# o_clone_rev_e.net
KiCad netlist of a schematic drawn in EAGLE
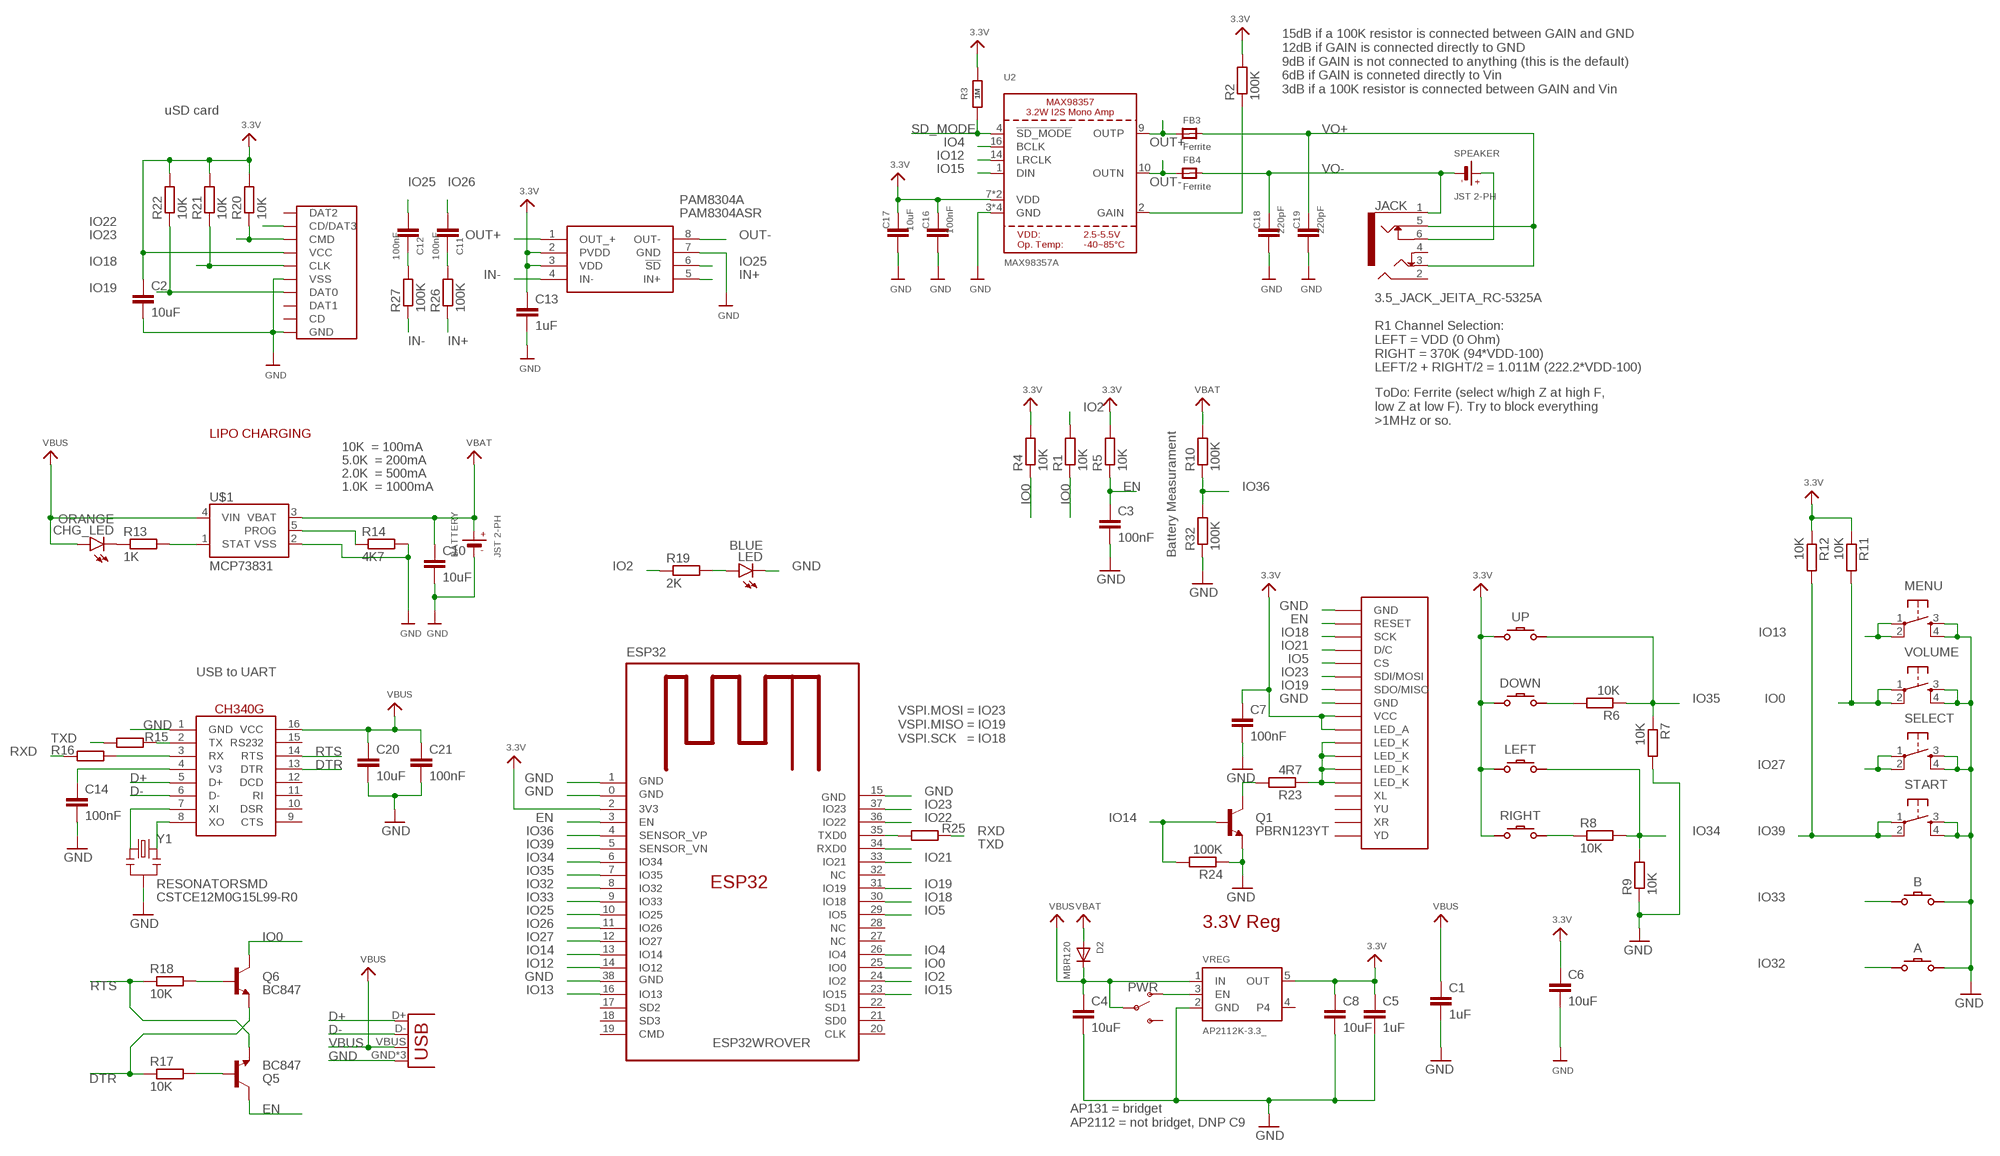
[diagram p0: schematic, sheet 1]

(export (version "E")
  (design (tool "Eeschema 10.0.6"))
  (components
    (comp (ref "A")
      (value "CONDUCTIVE_BUTTON")
      (footprint "eagle-import:CONDUCTIVE_BUTTON")
      (libsource (lib "eagle-import") (part "CONDUCTIVE_BUTTON"))
    )
    (comp (ref "B")
      (value "CONDUCTIVE_BUTTON")
      (footprint "eagle-import:CONDUCTIVE_BUTTON")
      (libsource (lib "eagle-import") (part "CONDUCTIVE_BUTTON"))
    )
    (comp (ref "BATTERY")
      (value "JST 2-PH")
      (footprint "eagle-import:JSTPH2")
      (libsource (lib "eagle-import") (part "JST_CONNECTOR"))
    )
    (comp (ref "C1")
      (value "1uF")
      (footprint "eagle-import:C0805K")
      (libsource (lib "eagle-import") (part "C-EUC0805K"))
    )
    (comp (ref "C2")
      (value "10uF")
      (footprint "eagle-import:C0805K")
      (libsource (lib "eagle-import") (part "C-EUC0805K"))
    )
    (comp (ref "C3")
      (value "100nF")
      (footprint "eagle-import:C0805K")
      (libsource (lib "eagle-import") (part "C-EUC0805K"))
    )
    (comp (ref "C4")
      (value "10uF")
      (footprint "eagle-import:C0805K")
      (libsource (lib "eagle-import") (part "C-EUC0805K"))
    )
    (comp (ref "C5")
      (value "1uF")
      (footprint "eagle-import:C0805K")
      (libsource (lib "eagle-import") (part "C-EUC0805K"))
    )
    (comp (ref "C6")
      (value "10uF")
      (footprint "eagle-import:C0805K")
      (libsource (lib "eagle-import") (part "C-EUC0805K"))
    )
    (comp (ref "C7")
      (value "100nF")
      (footprint "eagle-import:C0805")
      (libsource (lib "eagle-import") (part "C-EUC0805"))
    )
    (comp (ref "C8")
      (value "10uF")
      (footprint "eagle-import:C0805K")
      (libsource (lib "eagle-import") (part "C-EUC0805K"))
    )
    (comp (ref "C10")
      (value "10uF")
      (footprint "eagle-import:C0805K")
      (libsource (lib "eagle-import") (part "C-EUC0805K"))
    )
    (comp (ref "C11")
      (value "100nF")
      (footprint "eagle-import:C0805K")
      (libsource (lib "eagle-import") (part "C-EUC0805K"))
    )
    (comp (ref "C12")
      (value "100nF")
      (footprint "eagle-import:C0805K")
      (libsource (lib "eagle-import") (part "C-EUC0805K"))
    )
    (comp (ref "C13")
      (value "1uF")
      (footprint "eagle-import:C0805K")
      (libsource (lib "eagle-import") (part "C-EUC0805K"))
    )
    (comp (ref "C14")
      (value "100nF")
      (footprint "eagle-import:C0805K")
      (libsource (lib "eagle-import") (part "C-EUC0805K"))
    )
    (comp (ref "C16")
      (value "100nF")
      (footprint "eagle-import:C0805K")
      (libsource (lib "eagle-import") (part "C-EUC0805K"))
    )
    (comp (ref "C17")
      (value "10uF")
      (footprint "eagle-import:C0805K")
      (libsource (lib "eagle-import") (part "C-EUC0805K"))
    )
    (comp (ref "C18")
      (value "220pF")
      (footprint "eagle-import:C0805K")
      (libsource (lib "eagle-import") (part "C-EUC0805K"))
    )
    (comp (ref "C19")
      (value "220pF")
      (footprint "eagle-import:C0805K")
      (libsource (lib "eagle-import") (part "C-EUC0805K"))
    )
    (comp (ref "C20")
      (value "10uF")
      (footprint "eagle-import:C0805K")
      (libsource (lib "eagle-import") (part "C-EUC0805K"))
    )
    (comp (ref "C21")
      (value "100nF")
      (footprint "eagle-import:C0805K")
      (libsource (lib "eagle-import") (part "C-EUC0805K"))
    )
    (comp (ref "CHG_LED")
      (value "ORANGE")
      (footprint "eagle-import:CHIPLED_0805")
      (libsource (lib "eagle-import") (part "LEDCHIPLED_0805"))
    )
    (comp (ref "D2")
      (value "MBR120")
      (footprint "eagle-import:SOD-123")
      (libsource (lib "eagle-import") (part "DIODESOD-123"))
    )
    (comp (ref "DOWN")
      (value "CONDUCTIVE_BUTTON")
      (footprint "eagle-import:CONDUCTIVE_BUTTON")
      (libsource (lib "eagle-import") (part "CONDUCTIVE_BUTTON"))
    )
    (comp (ref "ESP32")
      (value "ESP32WROVER")
      (footprint "eagle-import:ESP32WROVER")
      (libsource (lib "eagle-import") (part "ESP32WROVER"))
    )
    (comp (ref "FB3")
      (value "Ferrite")
      (footprint "eagle-import:0805")
      (libsource (lib "eagle-import") (part "FERRITE0805"))
    )
    (comp (ref "FB4")
      (value "Ferrite")
      (footprint "eagle-import:0805")
      (libsource (lib "eagle-import") (part "FERRITE0805"))
    )
    (comp (ref "JACK")
      (value "3.5_JACK_JEITA_RC-5325A")
      (footprint "eagle-import:3.5_JACK_JEITA_RC-5325A")
      (libsource (lib "eagle-import") (part "3.5_JACK_JEITA_RC-5325A"))
    )
    (comp (ref "LCD")
      (value "ILI9341_3.2LCD_")
      (footprint "eagle-import:LI9341_3.2LCD")
      (libsource (lib "eagle-import") (part "ILI9341_3.2LCD_"))
    )
    (comp (ref "LED")
      (value "BLUE")
      (footprint "eagle-import:CHIPLED_0805")
      (libsource (lib "eagle-import") (part "LEDCHIPLED_0805"))
    )
    (comp (ref "LEFT")
      (value "CONDUCTIVE_BUTTON")
      (footprint "eagle-import:CONDUCTIVE_BUTTON")
      (libsource (lib "eagle-import") (part "CONDUCTIVE_BUTTON"))
    )
    (comp (ref "MENU")
      (value "TACTILE_SWITCHE_5X5_MICRO\"")
      (footprint "eagle-import:TACTILE_SWITCH_5X5_MICRO")
      (libsource (lib "eagle-import") (part "TACTILE_SWITCHE_5X5_MICRO{dblquote}"))
    )
    (comp (ref "PAM8304A")
      (value "PAM8304ASR")
      (footprint "eagle-import:SOP65P490X110-8N")
      (fields (field (name "MOUSER_PART_NUMBER") "621-PAM8304ASR"))
      (libsource (lib "eagle-import") (part "PAM8304ASR"))
    )
    (comp (ref "PWR")
      (value "SWITCH-SPDT-SMD-RIGHT-ANGLE")
      (footprint "eagle-import:SWITCH_SPST_SMD_A")
      (libsource (lib "eagle-import") (part "SWITCH-SPDT-SMD-RIGHT-ANGLE"))
    )
    (comp (ref "Q1")
      (value "PBRN123YT")
      (footprint "eagle-import:SOT23-3")
      (libsource (lib "eagle-import") (part "TRANSISTOR_NPNSOT23-3"))
    )
    (comp (ref "Q5")
      (value "BC847")
      (footprint "eagle-import:SOT23-3")
      (libsource (lib "eagle-import") (part "TRANSISTOR_NPNSOT23-3"))
    )
    (comp (ref "Q6")
      (value "BC847")
      (footprint "eagle-import:SOT23-3")
      (libsource (lib "eagle-import") (part "TRANSISTOR_NPNSOT23-3"))
    )
    (comp (ref "R1")
      (value "10K")
      (footprint "eagle-import:R0805")
      (libsource (lib "eagle-import") (part "R-EU_R0805"))
    )
    (comp (ref "R2")
      (value "100K")
      (footprint "eagle-import:R0805")
      (libsource (lib "eagle-import") (part "R-EU_R0805"))
    )
    (comp (ref "R3")
      (value "1M")
      (footprint "eagle-import:R0805")
      (libsource (lib "eagle-import") (part "R-EU_R0805"))
    )
    (comp (ref "R4")
      (value "10K")
      (footprint "eagle-import:R0805")
      (libsource (lib "eagle-import") (part "R-EU_R0805"))
    )
    (comp (ref "R5")
      (value "10K")
      (footprint "eagle-import:R0805")
      (libsource (lib "eagle-import") (part "R-EU_R0805"))
    )
    (comp (ref "R6")
      (value "10K")
      (footprint "eagle-import:R0805")
      (libsource (lib "eagle-import") (part "R-EU_R0805"))
    )
    (comp (ref "R7")
      (value "10K")
      (footprint "eagle-import:R0805")
      (libsource (lib "eagle-import") (part "R-EU_R0805"))
    )
    (comp (ref "R8")
      (value "10K")
      (footprint "eagle-import:R0805")
      (libsource (lib "eagle-import") (part "R-EU_R0805"))
    )
    (comp (ref "R9")
      (value "10K")
      (footprint "eagle-import:R0805")
      (libsource (lib "eagle-import") (part "R-EU_R0805"))
    )
    (comp (ref "R10")
      (value "100K")
      (footprint "eagle-import:R0805")
      (libsource (lib "eagle-import") (part "R-EU_R0805"))
    )
    (comp (ref "R11")
      (value "10K")
      (footprint "eagle-import:R0805")
      (libsource (lib "eagle-import") (part "R-EU_R0805"))
    )
    (comp (ref "R12")
      (value "10K")
      (footprint "eagle-import:R0805")
      (libsource (lib "eagle-import") (part "R-EU_R0805"))
    )
    (comp (ref "R13")
      (value "1K")
      (footprint "eagle-import:R0805")
      (libsource (lib "eagle-import") (part "R-EU_R0805"))
    )
    (comp (ref "R14")
      (value "4K7")
      (footprint "eagle-import:R0805")
      (libsource (lib "eagle-import") (part "R-EU_R0805"))
    )
    (comp (ref "R15")
      (value "470R")
      (footprint "eagle-import:R0805")
      (libsource (lib "eagle-import") (part "R-EU_R0805"))
    )
    (comp (ref "R16")
      (value "470R")
      (footprint "eagle-import:R0805")
      (libsource (lib "eagle-import") (part "R-EU_R0805"))
    )
    (comp (ref "R17")
      (value "10K")
      (footprint "eagle-import:R0805")
      (libsource (lib "eagle-import") (part "R-EU_R0805"))
    )
    (comp (ref "R18")
      (value "10K")
      (footprint "eagle-import:R0805")
      (libsource (lib "eagle-import") (part "R-EU_R0805"))
    )
    (comp (ref "R19")
      (value "2K")
      (footprint "eagle-import:R0805")
      (libsource (lib "eagle-import") (part "R-EU_R0805"))
    )
    (comp (ref "R20")
      (value "10K")
      (footprint "eagle-import:R0805")
      (libsource (lib "eagle-import") (part "R-EU_R0805"))
    )
    (comp (ref "R21")
      (value "10K")
      (footprint "eagle-import:R0805")
      (libsource (lib "eagle-import") (part "R-EU_R0805"))
    )
    (comp (ref "R22")
      (value "10K")
      (footprint "eagle-import:R0805")
      (libsource (lib "eagle-import") (part "R-EU_R0805"))
    )
    (comp (ref "R23")
      (value "4R7")
      (footprint "eagle-import:R0805")
      (libsource (lib "eagle-import") (part "R-EU_R0805"))
    )
    (comp (ref "R24")
      (value "100K")
      (footprint "eagle-import:R0805")
      (libsource (lib "eagle-import") (part "R-EU_R0805"))
    )
    (comp (ref "R25")
      (value "470R")
      (footprint "eagle-import:R0805")
      (libsource (lib "eagle-import") (part "R-EU_R0805"))
    )
    (comp (ref "R26")
      (value "100K")
      (footprint "eagle-import:R0805")
      (libsource (lib "eagle-import") (part "R-EU_R0805"))
    )
    (comp (ref "R27")
      (value "100K")
      (footprint "eagle-import:R0805")
      (libsource (lib "eagle-import") (part "R-EU_R0805"))
    )
    (comp (ref "R32")
      (value "100K")
      (footprint "eagle-import:R0805")
      (libsource (lib "eagle-import") (part "R-EU_R0805"))
    )
    (comp (ref "RIGHT")
      (value "CONDUCTIVE_BUTTON")
      (footprint "eagle-import:CONDUCTIVE_BUTTON")
      (libsource (lib "eagle-import") (part "CONDUCTIVE_BUTTON"))
    )
    (comp (ref "SD_CARD")
      (value "MICRO_SD_CARD\"")
      (footprint "eagle-import:TFP09-2--12B")
      (libsource (lib "eagle-import") (part "MICRO_SD_CARD{dblquote}"))
    )
    (comp (ref "SELECT")
      (value "TACTILE_SWITCHE_5X5_MICRO\"")
      (footprint "eagle-import:TACTILE_SWITCH_5X5_MICRO")
      (libsource (lib "eagle-import") (part "TACTILE_SWITCHE_5X5_MICRO{dblquote}"))
    )
    (comp (ref "SPEAKER")
      (value "JST 2-PH")
      (footprint "eagle-import:JSTPH2")
      (libsource (lib "eagle-import") (part "JST_CONNECTOR"))
    )
    (comp (ref "START")
      (value "TACTILE_SWITCHE_5X5_MICRO\"")
      (footprint "eagle-import:TACTILE_SWITCH_5X5_MICRO")
      (libsource (lib "eagle-import") (part "TACTILE_SWITCHE_5X5_MICRO{dblquote}"))
    )
    (comp (ref "U$1")
      (value "MCP73831")
      (footprint "eagle-import:SOT95P290X120-5")
      (libsource (lib "eagle-import") (part "MCP73831"))
    )
    (comp (ref "U$23")
      (value "CH340G")
      (footprint "eagle-import:SO16")
      (libsource (lib "eagle-import") (part "CH340G"))
    )
    (comp (ref "U2")
      (value "MAX98357A")
      (footprint "eagle-import:QFN16_3MM")
      (libsource (lib "eagle-import") (part "AUDIOAMP_MAX98357"))
    )
    (comp (ref "UP")
      (value "CONDUCTIVE_BUTTON")
      (footprint "eagle-import:CONDUCTIVE_BUTTON")
      (libsource (lib "eagle-import") (part "CONDUCTIVE_BUTTON"))
    )
    (comp (ref "USB")
      (value "USB_MICRO_ATTEND_")
      (footprint "eagle-import:USB_MICRO")
      (libsource (lib "eagle-import") (part "USB_MICRO_ATTEND_"))
    )
    (comp (ref "VOLUME")
      (value "TACTILE_SWITCHE_5X5_MICRO\"")
      (footprint "eagle-import:TACTILE_SWITCH_5X5_MICRO")
      (libsource (lib "eagle-import") (part "TACTILE_SWITCHE_5X5_MICRO{dblquote}"))
    )
    (comp (ref "VREG")
      (value "AP2112K-3.3_")
      (footprint "eagle-import:SOT95P290X120-5")
      (libsource (lib "eagle-import") (part "AP2112K-3.3_"))
    )
    (comp (ref "Y1")
      (value "RESONATORSMD")
      (footprint "eagle-import:RESONATOR-SMD")
      (libsource (lib "eagle-import") (part "RESONATORSMD"))
    )
  )
  (nets
    (net (code "1") (name "/D+") (class "Default")
      (node (ref "U$23") (pin "5") (pinfunction "D+_5") (pintype "bidirectional"))
      (node (ref "USB") (pin "D+") (pinfunction "D+_D+") (pintype "bidirectional"))
    )
    (net (code "2") (name "/D-") (class "Default")
      (node (ref "U$23") (pin "6") (pinfunction "D-_6") (pintype "bidirectional"))
      (node (ref "USB") (pin "D-") (pinfunction "D-_D-") (pintype "bidirectional"))
    )
    (net (code "3") (name "/DTR") (class "Default")
      (node (ref "Q6") (pin "2") (pinfunction "E_2") (pintype "passive"))
      (node (ref "R17") (pin "1") (pinfunction "1_1") (pintype "passive"))
      (node (ref "U$23") (pin "13") (pinfunction "DTR_13") (pintype "bidirectional"))
    )
    (net (code "4") (name "/EN") (class "Default")
      (node (ref "C3") (pin "1") (pinfunction "1_1") (pintype "passive"))
      (node (ref "ESP32") (pin "3") (pinfunction "EN_3") (pintype "bidirectional"))
      (node (ref "LCD") (pin "P$2") (pinfunction "RESET_P$2") (pintype "bidirectional"))
      (node (ref "Q5") (pin "3") (pinfunction "C_3") (pintype "passive"))
      (node (ref "R5") (pin "1") (pinfunction "1_1") (pintype "passive"))
    )
    (net (code "5") (name "/IN+") (class "Default")
      (node (ref "PAM8304A") (pin "5") (pinfunction "IN+_5") (pintype "bidirectional"))
      (node (ref "R26") (pin "1") (pinfunction "1_1") (pintype "passive"))
    )
    (net (code "6") (name "/IN-") (class "Default")
      (node (ref "PAM8304A") (pin "4") (pinfunction "IN-_4") (pintype "bidirectional"))
      (node (ref "R27") (pin "1") (pinfunction "1_1") (pintype "passive"))
    )
    (net (code "7") (name "/IO0") (class "Default")
      (node (ref "ESP32") (pin "25") (pinfunction "IO0_25") (pintype "bidirectional"))
      (node (ref "Q6") (pin "3") (pinfunction "C_3") (pintype "passive"))
      (node (ref "R1") (pin "1") (pinfunction "1_1") (pintype "passive"))
      (node (ref "R11") (pin "2") (pinfunction "2_2") (pintype "passive"))
      (node (ref "R4") (pin "1") (pinfunction "1_1") (pintype "passive"))
      (node (ref "VOLUME") (pin "1") (pinfunction "1_1") (pintype "passive"))
      (node (ref "VOLUME") (pin "2") (pinfunction "2_2") (pintype "passive"))
    )
    (net (code "8") (name "/IO2") (class "Default")
      (node (ref "ESP32") (pin "24") (pinfunction "IO2_24") (pintype "bidirectional"))
      (node (ref "R1") (pin "2") (pinfunction "2_2") (pintype "passive"))
      (node (ref "R19") (pin "1") (pinfunction "1_1") (pintype "passive"))
    )
    (net (code "9") (name "/IO4") (class "Default")
      (node (ref "ESP32") (pin "26") (pinfunction "IO4_26") (pintype "bidirectional"))
      (node (ref "U2") (pin "16") (pinfunction "BCLK_16") (pintype "bidirectional"))
    )
    (net (code "10") (name "/IO5") (class "Default")
      (node (ref "ESP32") (pin "29") (pinfunction "IO5_29") (pintype "bidirectional"))
      (node (ref "LCD") (pin "P$5") (pinfunction "CS_P$5") (pintype "bidirectional"))
    )
    (net (code "11") (name "/IO12") (class "Default")
      (node (ref "ESP32") (pin "14") (pinfunction "IO12_14") (pintype "bidirectional"))
      (node (ref "U2") (pin "14") (pinfunction "LRCLK_14") (pintype "bidirectional"))
    )
    (net (code "12") (name "/IO13") (class "Default")
      (node (ref "ESP32") (pin "16") (pinfunction "IO13_16") (pintype "bidirectional"))
      (node (ref "MENU") (pin "1") (pinfunction "1_1") (pintype "passive"))
      (node (ref "MENU") (pin "2") (pinfunction "2_2") (pintype "passive"))
    )
    (net (code "13") (name "/IO14") (class "Default")
      (node (ref "ESP32") (pin "13") (pinfunction "IO14_13") (pintype "bidirectional"))
      (node (ref "Q1") (pin "1") (pinfunction "B_1") (pintype "passive"))
      (node (ref "R24") (pin "2") (pinfunction "2_2") (pintype "passive"))
    )
    (net (code "14") (name "/IO15") (class "Default")
      (node (ref "ESP32") (pin "23") (pinfunction "IO15_23") (pintype "bidirectional"))
      (node (ref "U2") (pin "1") (pinfunction "DIN_1") (pintype "bidirectional"))
    )
    (net (code "15") (name "/IO18") (class "Default")
      (node (ref "ESP32") (pin "30") (pinfunction "IO18_30") (pintype "bidirectional"))
      (node (ref "LCD") (pin "P$3") (pinfunction "SCK_P$3") (pintype "bidirectional"))
      (node (ref "R21") (pin "1") (pinfunction "1_1") (pintype "passive"))
      (node (ref "SD_CARD") (pin "CLK") (pinfunction "CLK_CLK") (pintype "bidirectional"))
    )
    (net (code "16") (name "/IO19") (class "Default")
      (node (ref "ESP32") (pin "31") (pinfunction "IO19_31") (pintype "bidirectional"))
      (node (ref "LCD") (pin "P$7") (pinfunction "SDO/MISO_P$7") (pintype "bidirectional"))
      (node (ref "R22") (pin "1") (pinfunction "1_1") (pintype "passive"))
      (node (ref "SD_CARD") (pin "DAT0") (pinfunction "DAT0_DAT0") (pintype "bidirectional"))
    )
    (net (code "17") (name "/IO21") (class "Default")
      (node (ref "ESP32") (pin "33") (pinfunction "IO21_33") (pintype "bidirectional"))
      (node (ref "LCD") (pin "P$4") (pinfunction "D/C_P$4") (pintype "bidirectional"))
    )
    (net (code "18") (name "/IO22") (class "Default")
      (node (ref "ESP32") (pin "36") (pinfunction "IO22_36") (pintype "bidirectional"))
      (node (ref "SD_CARD") (pin "CD/DAT3") (pinfunction "CD/DAT3_CD/DAT3") (pintype "bidirectional"))
    )
    (net (code "19") (name "/IO23") (class "Default")
      (node (ref "ESP32") (pin "37") (pinfunction "IO23_37") (pintype "bidirectional"))
      (node (ref "LCD") (pin "P$6") (pinfunction "SDI/MOSI_P$6") (pintype "bidirectional"))
      (node (ref "R20") (pin "1") (pinfunction "1_1") (pintype "passive"))
      (node (ref "SD_CARD") (pin "CMD") (pinfunction "CMD_CMD") (pintype "bidirectional"))
    )
    (net (code "20") (name "/IO25") (class "Default")
      (node (ref "C12") (pin "2") (pinfunction "2_2") (pintype "passive"))
      (node (ref "ESP32") (pin "10") (pinfunction "IO25_10") (pintype "bidirectional"))
      (node (ref "PAM8304A") (pin "6") (pinfunction "~{SD}_6") (pintype "bidirectional"))
    )
    (net (code "21") (name "/IO26") (class "Default")
      (node (ref "C11") (pin "2") (pinfunction "2_2") (pintype "passive"))
      (node (ref "ESP32") (pin "11") (pinfunction "IO26_11") (pintype "bidirectional"))
    )
    (net (code "22") (name "/IO27") (class "Default")
      (node (ref "ESP32") (pin "12") (pinfunction "IO27_12") (pintype "bidirectional"))
      (node (ref "SELECT") (pin "1") (pinfunction "1_1") (pintype "passive"))
      (node (ref "SELECT") (pin "2") (pinfunction "2_2") (pintype "passive"))
    )
    (net (code "23") (name "/IO32") (class "Default")
      (node (ref "A") (pin "P$1") (pinfunction "P$1_P$1") (pintype "bidirectional"))
      (node (ref "ESP32") (pin "8") (pinfunction "IO32_8") (pintype "bidirectional"))
    )
    (net (code "24") (name "/IO33") (class "Default")
      (node (ref "B") (pin "P$1") (pinfunction "P$1_P$1") (pintype "bidirectional"))
      (node (ref "ESP32") (pin "9") (pinfunction "IO33_9") (pintype "bidirectional"))
    )
    (net (code "25") (name "/IO34") (class "Default")
      (node (ref "ESP32") (pin "6") (pinfunction "IO34_6") (pintype "bidirectional"))
      (node (ref "LEFT") (pin "P$2") (pinfunction "P$2_P$2") (pintype "bidirectional"))
      (node (ref "R8") (pin "2") (pinfunction "2_2") (pintype "passive"))
      (node (ref "R9") (pin "2") (pinfunction "2_2") (pintype "passive"))
    )
    (net (code "26") (name "/IO35") (class "Default")
      (node (ref "ESP32") (pin "7") (pinfunction "IO35_7") (pintype "bidirectional"))
      (node (ref "R6") (pin "1") (pinfunction "1_1") (pintype "passive"))
      (node (ref "R7") (pin "1") (pinfunction "1_1") (pintype "passive"))
      (node (ref "UP") (pin "P$2") (pinfunction "P$2_P$2") (pintype "bidirectional"))
    )
    (net (code "27") (name "/IO36") (class "Default")
      (node (ref "ESP32") (pin "4") (pinfunction "SENSOR_VP_4") (pintype "bidirectional"))
      (node (ref "R10") (pin "1") (pinfunction "1_1") (pintype "passive"))
      (node (ref "R32") (pin "2") (pinfunction "2_2") (pintype "passive"))
    )
    (net (code "28") (name "/IO39") (class "Default")
      (node (ref "ESP32") (pin "5") (pinfunction "SENSOR_VN_5") (pintype "bidirectional"))
      (node (ref "R12") (pin "2") (pinfunction "2_2") (pintype "passive"))
      (node (ref "START") (pin "1") (pinfunction "1_1") (pintype "passive"))
      (node (ref "START") (pin "2") (pinfunction "2_2") (pintype "passive"))
    )
    (net (code "29") (name "/OUT+") (class "Default")
      (node (ref "FB3") (pin "1") (pinfunction "P$1_1") (pintype "passive"))
      (node (ref "PAM8304A") (pin "1") (pinfunction "OUT_+_1") (pintype "bidirectional"))
      (node (ref "U2") (pin "9") (pinfunction "OUTP_9") (pintype "output"))
    )
    (net (code "30") (name "/OUT-") (class "Default")
      (node (ref "FB4") (pin "1") (pinfunction "P$1_1") (pintype "passive"))
      (node (ref "PAM8304A") (pin "8") (pinfunction "OUT-_8") (pintype "bidirectional"))
      (node (ref "U2") (pin "10") (pinfunction "OUTN_10") (pintype "output"))
    )
    (net (code "31") (name "/RTS") (class "Default")
      (node (ref "Q5") (pin "2") (pinfunction "E_2") (pintype "passive"))
      (node (ref "R18") (pin "1") (pinfunction "1_1") (pintype "passive"))
      (node (ref "U$23") (pin "14") (pinfunction "RTS_14") (pintype "bidirectional"))
    )
    (net (code "32") (name "/RXD") (class "Default")
      (node (ref "R16") (pin "2") (pinfunction "2_2") (pintype "passive"))
      (node (ref "R25") (pin "1") (pinfunction "1_1") (pintype "passive"))
    )
    (net (code "33") (name "/SD_MODE") (class "Default")
      (node (ref "R3") (pin "1") (pinfunction "1_1") (pintype "passive"))
      (node (ref "U2") (pin "4") (pinfunction "~{SD_MODE}_4") (pintype "bidirectional"))
    )
    (net (code "34") (name "/TXD") (class "Default")
      (node (ref "ESP32") (pin "34") (pinfunction "RXD0_34") (pintype "bidirectional"))
      (node (ref "R15") (pin "2") (pinfunction "2_2") (pintype "passive"))
    )
    (net (code "35") (name "/VO+") (class "Default")
      (node (ref "C19") (pin "1") (pinfunction "1_1") (pintype "passive"))
      (node (ref "FB3") (pin "2") (pinfunction "P$2_2") (pintype "passive"))
      (node (ref "JACK") (pin "3") (pinfunction "3_3") (pintype "bidirectional"))
      (node (ref "JACK") (pin "5") (pinfunction "5_5") (pintype "bidirectional"))
    )
    (net (code "36") (name "/VO-") (class "Default")
      (node (ref "C18") (pin "1") (pinfunction "1_1") (pintype "passive"))
      (node (ref "FB4") (pin "2") (pinfunction "P$2_2") (pintype "passive"))
      (node (ref "JACK") (pin "1") (pinfunction "1_1") (pintype "bidirectional"))
      (node (ref "SPEAKER") (pin "1") (pinfunction "-_1") (pintype "passive"))
    )
    (net (code "37") (name "3.3V") (class "Default")
      (node (ref "C13") (pin "1") (pinfunction "1_1") (pintype "passive"))
      (node (ref "C16") (pin "1") (pinfunction "1_1") (pintype "passive"))
      (node (ref "C17") (pin "1") (pinfunction "1_1") (pintype "passive"))
      (node (ref "C2") (pin "1") (pinfunction "1_1") (pintype "passive"))
      (node (ref "C5") (pin "1") (pinfunction "1_1") (pintype "passive"))
      (node (ref "C6") (pin "1") (pinfunction "1_1") (pintype "passive"))
      (node (ref "C7") (pin "1") (pinfunction "1_1") (pintype "passive"))
      (node (ref "C8") (pin "1") (pinfunction "1_1") (pintype "passive"))
      (node (ref "DOWN") (pin "P$1") (pinfunction "P$1_P$1") (pintype "bidirectional"))
      (node (ref "ESP32") (pin "2") (pinfunction "3V3_2") (pintype "power_in"))
      (node (ref "LCD") (pin "P$10") (pinfunction "LED_A_P$10") (pintype "bidirectional"))
      (node (ref "LCD") (pin "P$9") (pinfunction "VCC_P$9") (pintype "bidirectional"))
      (node (ref "LEFT") (pin "P$1") (pinfunction "P$1_P$1") (pintype "bidirectional"))
      (node (ref "PAM8304A") (pin "2") (pinfunction "PVDD_2") (pintype "bidirectional"))
      (node (ref "PAM8304A") (pin "3") (pinfunction "VDD_3") (pintype "bidirectional"))
      (node (ref "R11") (pin "1") (pinfunction "1_1") (pintype "passive"))
      (node (ref "R12") (pin "1") (pinfunction "1_1") (pintype "passive"))
      (node (ref "R2") (pin "2") (pinfunction "2_2") (pintype "passive"))
      (node (ref "R20") (pin "2") (pinfunction "2_2") (pintype "passive"))
      (node (ref "R21") (pin "2") (pinfunction "2_2") (pintype "passive"))
      (node (ref "R22") (pin "2") (pinfunction "2_2") (pintype "passive"))
      (node (ref "R3") (pin "2") (pinfunction "2_2") (pintype "passive"))
      (node (ref "R4") (pin "2") (pinfunction "2_2") (pintype "passive"))
      (node (ref "R5") (pin "2") (pinfunction "2_2") (pintype "passive"))
      (node (ref "RIGHT") (pin "P$1") (pinfunction "P$1_P$1") (pintype "bidirectional"))
      (node (ref "SD_CARD") (pin "VCC") (pinfunction "VCC_VCC") (pintype "bidirectional"))
      (node (ref "U2") (pin "7") (pinfunction "VDD_7") (pintype "power_in"))
      (node (ref "U2") (pin "8") (pinfunction "VDD_8") (pintype "power_in"))
      (node (ref "UP") (pin "P$1") (pinfunction "P$1_P$1") (pintype "bidirectional"))
      (node (ref "VREG") (pin "5") (pinfunction "OUT_5") (pintype "bidirectional"))
    )
    (net (code "38") (name "GND") (class "Default")
      (node (ref "A") (pin "P$2") (pinfunction "P$2_P$2") (pintype "bidirectional"))
      (node (ref "B") (pin "P$2") (pinfunction "P$2_P$2") (pintype "bidirectional"))
      (node (ref "BATTERY") (pin "1") (pinfunction "-_1") (pintype "passive"))
      (node (ref "C1") (pin "2") (pinfunction "2_2") (pintype "passive"))
      (node (ref "C10") (pin "2") (pinfunction "2_2") (pintype "passive"))
      (node (ref "C13") (pin "2") (pinfunction "2_2") (pintype "passive"))
      (node (ref "C14") (pin "2") (pinfunction "2_2") (pintype "passive"))
      (node (ref "C16") (pin "2") (pinfunction "2_2") (pintype "passive"))
      (node (ref "C17") (pin "2") (pinfunction "2_2") (pintype "passive"))
      (node (ref "C18") (pin "2") (pinfunction "2_2") (pintype "passive"))
      (node (ref "C19") (pin "2") (pinfunction "2_2") (pintype "passive"))
      (node (ref "C2") (pin "2") (pinfunction "2_2") (pintype "passive"))
      (node (ref "C20") (pin "2") (pinfunction "2_2") (pintype "passive"))
      (node (ref "C21") (pin "2") (pinfunction "2_2") (pintype "passive"))
      (node (ref "C3") (pin "2") (pinfunction "2_2") (pintype "passive"))
      (node (ref "C4") (pin "2") (pinfunction "2_2") (pintype "passive"))
      (node (ref "C5") (pin "2") (pinfunction "2_2") (pintype "passive"))
      (node (ref "C6") (pin "2") (pinfunction "2_2") (pintype "passive"))
      (node (ref "C7") (pin "2") (pinfunction "2_2") (pintype "passive"))
      (node (ref "C8") (pin "2") (pinfunction "2_2") (pintype "passive"))
      (node (ref "ESP32") (pin "0") (pinfunction "GND_0") (pintype "power_in"))
      (node (ref "ESP32") (pin "1") (pinfunction "GND_1") (pintype "power_in"))
      (node (ref "ESP32") (pin "15") (pinfunction "GND_15") (pintype "power_in"))
      (node (ref "ESP32") (pin "38") (pinfunction "GND_38") (pintype "power_in"))
      (node (ref "LCD") (pin "P$1") (pinfunction "GND_P$1") (pintype "bidirectional"))
      (node (ref "LCD") (pin "P$8") (pinfunction "GND_P$8") (pintype "bidirectional"))
      (node (ref "LED") (pin "C") (pinfunction "C_C") (pintype "passive"))
      (node (ref "MENU") (pin "3") (pinfunction "3_3") (pintype "passive"))
      (node (ref "MENU") (pin "4") (pinfunction "4_4") (pintype "passive"))
      (node (ref "PAM8304A") (pin "7") (pinfunction "GND_7") (pintype "bidirectional"))
      (node (ref "Q1") (pin "2") (pinfunction "E_2") (pintype "passive"))
      (node (ref "R14") (pin "2") (pinfunction "2_2") (pintype "passive"))
      (node (ref "R24") (pin "1") (pinfunction "1_1") (pintype "passive"))
      (node (ref "R32") (pin "1") (pinfunction "1_1") (pintype "passive"))
      (node (ref "R7") (pin "2") (pinfunction "2_2") (pintype "passive"))
      (node (ref "R9") (pin "1") (pinfunction "1_1") (pintype "passive"))
      (node (ref "SD_CARD") (pin "GND") (pinfunction "GND_GND") (pintype "bidirectional"))
      (node (ref "SD_CARD") (pin "GND@1") (pinfunction "GND_GND@1") (pintype "bidirectional"))
      (node (ref "SD_CARD") (pin "GND@2") (pinfunction "GND_GND@2") (pintype "bidirectional"))
      (node (ref "SD_CARD") (pin "GND@3") (pinfunction "VSS_GND@3") (pintype "bidirectional"))
      (node (ref "SD_CARD") (pin "VSS") (pinfunction "GND_VSS") (pintype "bidirectional"))
      (node (ref "SELECT") (pin "3") (pinfunction "3_3") (pintype "passive"))
      (node (ref "SELECT") (pin "4") (pinfunction "4_4") (pintype "passive"))
      (node (ref "START") (pin "3") (pinfunction "3_3") (pintype "passive"))
      (node (ref "START") (pin "4") (pinfunction "4_4") (pintype "passive"))
      (node (ref "U$1") (pin "2") (pinfunction "VSS_2") (pintype "power_in"))
      (node (ref "U$23") (pin "1") (pinfunction "GND_1") (pintype "bidirectional"))
      (node (ref "U2") (pin "11") (pinfunction "GND_11") (pintype "power_in"))
      (node (ref "U2") (pin "15") (pinfunction "GND_15") (pintype "power_in"))
      (node (ref "U2") (pin "3") (pinfunction "GND_3") (pintype "power_in"))
      (node (ref "U2") (pin "THERMAL") (pinfunction "GND_THERMAL") (pintype "power_in"))
      (node (ref "USB") (pin "GND") (pinfunction "GND_GND") (pintype "bidirectional"))
      (node (ref "USB") (pin "GND@2") (pinfunction "GND_GND@2") (pintype "bidirectional"))
      (node (ref "USB") (pin "GND@3") (pinfunction "GND_GND@3") (pintype "bidirectional"))
      (node (ref "VOLUME") (pin "3") (pinfunction "3_3") (pintype "passive"))
      (node (ref "VOLUME") (pin "4") (pinfunction "4_4") (pintype "passive"))
      (node (ref "VREG") (pin "2") (pinfunction "GND_2") (pintype "bidirectional"))
      (node (ref "Y1") (pin "2") (pinfunction "2_2") (pintype "passive"))
    )
    (net (code "39") (name "Net-(C11-Pad1)") (class "Default")
      (node (ref "C11") (pin "1") (pinfunction "1_1") (pintype "passive"))
      (node (ref "R26") (pin "2") (pinfunction "2_2") (pintype "passive"))
    )
    (net (code "40") (name "Net-(C12-Pad1)") (class "Default")
      (node (ref "C12") (pin "1") (pinfunction "1_1") (pintype "passive"))
      (node (ref "R27") (pin "2") (pinfunction "2_2") (pintype "passive"))
    )
    (net (code "41") (name "Net-(CHG_LED-PadC)") (class "Default")
      (node (ref "CHG_LED") (pin "C") (pinfunction "C_C") (pintype "passive"))
      (node (ref "R13") (pin "1") (pinfunction "1_1") (pintype "passive"))
    )
    (net (code "42") (name "Net-(DOWN-PadP$2)") (class "Default")
      (node (ref "DOWN") (pin "P$2") (pinfunction "P$2_P$2") (pintype "bidirectional"))
      (node (ref "R6") (pin "2") (pinfunction "2_2") (pintype "passive"))
    )
    (net (code "43") (name "Net-(ESP32-TXD0)") (class "Default")
      (node (ref "ESP32") (pin "35") (pinfunction "TXD0_35") (pintype "bidirectional"))
      (node (ref "R25") (pin "2") (pinfunction "2_2") (pintype "passive"))
    )
    (net (code "44") (name "Net-(LCD-LED_K-PadP$11)") (class "Default")
      (node (ref "LCD") (pin "P$11") (pinfunction "LED_K_P$11") (pintype "bidirectional"))
      (node (ref "LCD") (pin "P$12") (pinfunction "LED_K_P$12") (pintype "bidirectional"))
      (node (ref "LCD") (pin "P$13") (pinfunction "LED_K_P$13") (pintype "bidirectional"))
      (node (ref "LCD") (pin "P$14") (pinfunction "LED_K_P$14") (pintype "bidirectional"))
      (node (ref "R23") (pin "1") (pinfunction "1_1") (pintype "passive"))
    )
    (net (code "45") (name "Net-(LED-PadA)") (class "Default")
      (node (ref "LED") (pin "A") (pinfunction "A_A") (pintype "passive"))
      (node (ref "R19") (pin "2") (pinfunction "2_2") (pintype "passive"))
    )
    (net (code "46") (name "Net-(PWR-O)") (class "Default")
      (node (ref "PWR") (pin "1") (pinfunction "O_1") (pintype "passive"))
      (node (ref "VREG") (pin "3") (pinfunction "EN_3") (pintype "bidirectional"))
    )
    (net (code "47") (name "Net-(Q1-C)") (class "Default")
      (node (ref "Q1") (pin "3") (pinfunction "C_3") (pintype "passive"))
      (node (ref "R23") (pin "2") (pinfunction "2_2") (pintype "passive"))
    )
    (net (code "48") (name "Net-(Q5-B)") (class "Default")
      (node (ref "Q5") (pin "1") (pinfunction "B_1") (pintype "passive"))
      (node (ref "R17") (pin "2") (pinfunction "2_2") (pintype "passive"))
    )
    (net (code "49") (name "Net-(Q6-B)") (class "Default")
      (node (ref "Q6") (pin "1") (pinfunction "B_1") (pintype "passive"))
      (node (ref "R18") (pin "2") (pinfunction "2_2") (pintype "passive"))
    )
    (net (code "50") (name "Net-(R8-Pad1)") (class "Default")
      (node (ref "R8") (pin "1") (pinfunction "1_1") (pintype "passive"))
      (node (ref "RIGHT") (pin "P$2") (pinfunction "P$2_P$2") (pintype "bidirectional"))
    )
    (net (code "51") (name "Net-(SPEAKER-+)") (class "Default")
      (node (ref "JACK") (pin "6") (pinfunction "6_6") (pintype "bidirectional"))
      (node (ref "SPEAKER") (pin "2") (pinfunction "+_2") (pintype "passive"))
    )
    (net (code "52") (name "Net-(U$1-PROG)") (class "Default")
      (node (ref "R14") (pin "1") (pinfunction "1_1") (pintype "passive"))
      (node (ref "U$1") (pin "5") (pinfunction "PROG_5") (pintype "input"))
    )
    (net (code "53") (name "Net-(U$1-STAT)") (class "Default")
      (node (ref "R13") (pin "2") (pinfunction "2_2") (pintype "passive"))
      (node (ref "U$1") (pin "1") (pinfunction "STAT_1") (pintype "output"))
    )
    (net (code "54") (name "Net-(U$23-RX)") (class "Default")
      (node (ref "R16") (pin "1") (pinfunction "1_1") (pintype "passive"))
      (node (ref "U$23") (pin "3") (pinfunction "RX_3") (pintype "bidirectional"))
    )
    (net (code "55") (name "Net-(U$23-TX)") (class "Default")
      (node (ref "R15") (pin "1") (pinfunction "1_1") (pintype "passive"))
      (node (ref "U$23") (pin "2") (pinfunction "TX_2") (pintype "bidirectional"))
    )
    (net (code "56") (name "Net-(U$23-V3)") (class "Default")
      (node (ref "C14") (pin "1") (pinfunction "1_1") (pintype "passive"))
      (node (ref "U$23") (pin "4") (pinfunction "V3_4") (pintype "bidirectional"))
    )
    (net (code "57") (name "Net-(U$23-XI)") (class "Default")
      (node (ref "U$23") (pin "7") (pinfunction "XI_7") (pintype "bidirectional"))
      (node (ref "Y1") (pin "1") (pinfunction "1_1") (pintype "passive"))
    )
    (net (code "58") (name "Net-(U$23-XO)") (class "Default")
      (node (ref "U$23") (pin "8") (pinfunction "XO_8") (pintype "bidirectional"))
      (node (ref "Y1") (pin "3") (pinfunction "3_3") (pintype "passive"))
    )
    (net (code "59") (name "Net-(U2-GAIN)") (class "Default")
      (node (ref "R2") (pin "1") (pinfunction "1_1") (pintype "passive"))
      (node (ref "U2") (pin "2") (pinfunction "GAIN_2") (pintype "bidirectional"))
    )
    (net (code "60") (name "VBAT") (class "Default")
      (node (ref "BATTERY") (pin "2") (pinfunction "+_2") (pintype "passive"))
      (node (ref "C10") (pin "1") (pinfunction "1_1") (pintype "passive"))
      (node (ref "D2") (pin "A") (pinfunction "A_A") (pintype "passive"))
      (node (ref "R10") (pin "2") (pinfunction "2_2") (pintype "passive"))
      (node (ref "U$1") (pin "3") (pinfunction "VBAT_3") (pintype "power_in"))
    )
    (net (code "61") (name "VBUS") (class "Default")
      (node (ref "C1") (pin "1") (pinfunction "1_1") (pintype "passive"))
      (node (ref "C20") (pin "1") (pinfunction "1_1") (pintype "passive"))
      (node (ref "C21") (pin "1") (pinfunction "1_1") (pintype "passive"))
      (node (ref "C4") (pin "1") (pinfunction "1_1") (pintype "passive"))
      (node (ref "CHG_LED") (pin "A") (pinfunction "A_A") (pintype "passive"))
      (node (ref "D2") (pin "C") (pinfunction "C_C") (pintype "passive"))
      (node (ref "PWR") (pin "2") (pinfunction "P_2") (pintype "passive"))
      (node (ref "U$1") (pin "4") (pinfunction "VIN_4") (pintype "power_in"))
      (node (ref "U$23") (pin "16") (pinfunction "VCC_16") (pintype "bidirectional"))
      (node (ref "USB") (pin "VBUS") (pinfunction "VBUS_VBUS") (pintype "bidirectional"))
      (node (ref "VREG") (pin "1") (pinfunction "IN_1") (pintype "bidirectional"))
    )
    (net (code "62") (name "unconnected-(ESP32-CLK-Pad20)") (class "Default")
      (node (ref "ESP32") (pin "20") (pinfunction "CLK_20") (pintype "bidirectional"))
    )
    (net (code "63") (name "unconnected-(ESP32-CMD-Pad19)") (class "Default")
      (node (ref "ESP32") (pin "19") (pinfunction "CMD_19") (pintype "bidirectional"))
    )
    (net (code "64") (name "unconnected-(ESP32-NC-Pad27)") (class "Default")
      (node (ref "ESP32") (pin "27") (pinfunction "NC_27") (pintype "bidirectional"))
    )
    (net (code "65") (name "unconnected-(ESP32-NC-Pad28)") (class "Default")
      (node (ref "ESP32") (pin "28") (pinfunction "NC_28") (pintype "bidirectional"))
    )
    (net (code "66") (name "unconnected-(ESP32-NC-Pad32)") (class "Default")
      (node (ref "ESP32") (pin "32") (pinfunction "NC_32") (pintype "bidirectional"))
    )
    (net (code "67") (name "unconnected-(ESP32-SD0-Pad21)") (class "Default")
      (node (ref "ESP32") (pin "21") (pinfunction "SD0_21") (pintype "bidirectional"))
    )
    (net (code "68") (name "unconnected-(ESP32-SD1-Pad22)") (class "Default")
      (node (ref "ESP32") (pin "22") (pinfunction "SD1_22") (pintype "bidirectional"))
    )
    (net (code "69") (name "unconnected-(ESP32-SD2-Pad17)") (class "Default")
      (node (ref "ESP32") (pin "17") (pinfunction "SD2_17") (pintype "bidirectional"))
    )
    (net (code "70") (name "unconnected-(ESP32-SD3-Pad18)") (class "Default")
      (node (ref "ESP32") (pin "18") (pinfunction "SD3_18") (pintype "bidirectional"))
    )
    (net (code "71") (name "unconnected-(JACK-Pad2)") (class "Default")
      (node (ref "JACK") (pin "2") (pinfunction "2_2") (pintype "bidirectional"))
    )
    (net (code "72") (name "unconnected-(JACK-Pad4)") (class "Default")
      (node (ref "JACK") (pin "4") (pinfunction "4_4") (pintype "bidirectional"))
    )
    (net (code "73") (name "unconnected-(LCD-XL-PadP$15)") (class "Default")
      (node (ref "LCD") (pin "P$15") (pinfunction "XL_P$15") (pintype "bidirectional"))
    )
    (net (code "74") (name "unconnected-(LCD-XR-PadP$16)") (class "Default")
      (node (ref "LCD") (pin "P$16") (pinfunction "XR_P$16") (pintype "bidirectional"))
    )
    (net (code "75") (name "unconnected-(LCD-YD-PadP$17)") (class "Default")
      (node (ref "LCD") (pin "P$17") (pinfunction "YD_P$17") (pintype "bidirectional"))
    )
    (net (code "76") (name "unconnected-(LCD-YU-PadP$18)") (class "Default")
      (node (ref "LCD") (pin "P$18") (pinfunction "YU_P$18") (pintype "bidirectional"))
    )
    (net (code "77") (name "unconnected-(PWR-S-Pad3)") (class "Default")
      (node (ref "PWR") (pin "3") (pinfunction "S_3") (pintype "passive"))
    )
    (net (code "78") (name "unconnected-(SD_CARD-PadCD)") (class "Default")
      (node (ref "SD_CARD") (pin "CD") (pinfunction "CD_CD") (pintype "bidirectional"))
    )
    (net (code "79") (name "unconnected-(SD_CARD-PadDAT1)") (class "Default")
      (node (ref "SD_CARD") (pin "DAT1") (pinfunction "DAT1_DAT1") (pintype "bidirectional"))
    )
    (net (code "80") (name "unconnected-(SD_CARD-PadDAT2)") (class "Default")
      (node (ref "SD_CARD") (pin "DAT2") (pinfunction "DAT2_DAT2") (pintype "bidirectional"))
    )
    (net (code "81") (name "unconnected-(U$23-CTS-Pad9)") (class "Default")
      (node (ref "U$23") (pin "9") (pinfunction "CTS_9") (pintype "bidirectional"))
    )
    (net (code "82") (name "unconnected-(U$23-DCD-Pad12)") (class "Default")
      (node (ref "U$23") (pin "12") (pinfunction "DCD_12") (pintype "bidirectional"))
    )
    (net (code "83") (name "unconnected-(U$23-DSR-Pad10)") (class "Default")
      (node (ref "U$23") (pin "10") (pinfunction "DSR_10") (pintype "bidirectional"))
    )
    (net (code "84") (name "unconnected-(U$23-RI-Pad11)") (class "Default")
      (node (ref "U$23") (pin "11") (pinfunction "RI_11") (pintype "bidirectional"))
    )
    (net (code "85") (name "unconnected-(U$23-RS232-Pad15)") (class "Default")
      (node (ref "U$23") (pin "15") (pinfunction "RS232_15") (pintype "bidirectional"))
    )
    (net (code "86") (name "unconnected-(VREG-P4-Pad4)") (class "Default")
      (node (ref "VREG") (pin "4") (pinfunction "P4_4") (pintype "bidirectional"))
    )
  )
)
